# OLED_PCB_Dual_Rev1_1.net
KiCad netlist of a schematic drawn in Altium Designer
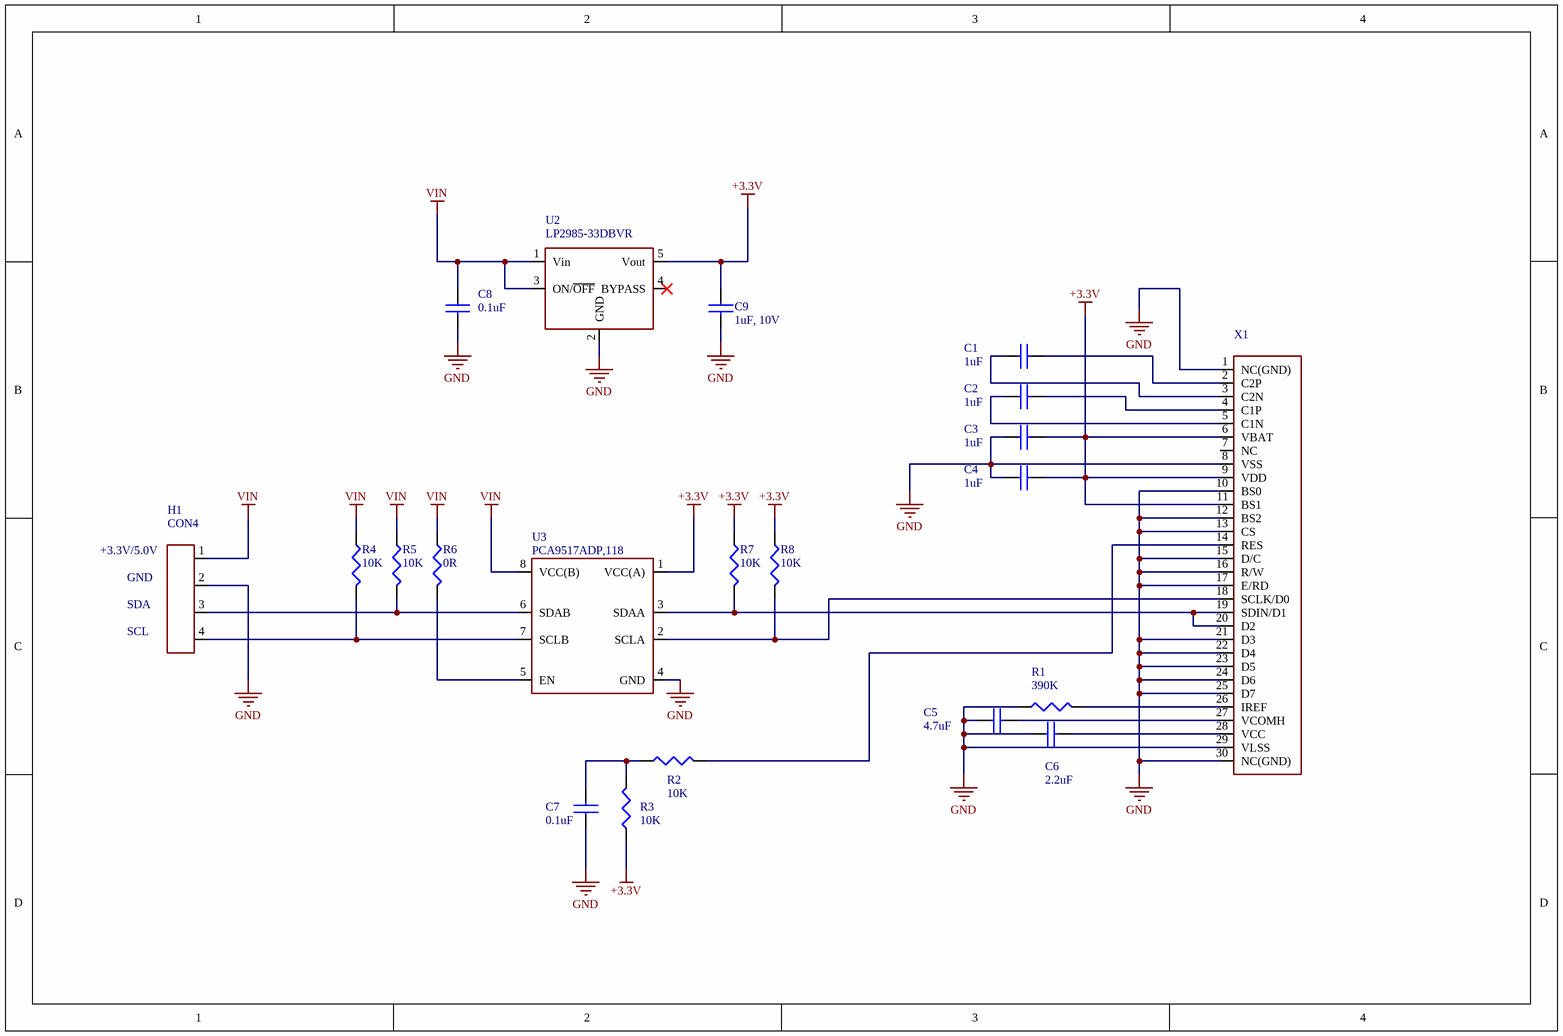
[diagram p0: OLED_PCB_Dual_Rev1_1.SchDoc]

(export (version "E")
  (design (tool "Eeschema 10.0.6"))
  (components
    (comp (ref "C1")
      (value "1uF")
      (footprint "CAPC1608X90N")
      (description "CAP 0603")
      (libsource (lib "Parts_Library") (part "CAP_0603"))
    )
    (comp (ref "C2")
      (value "1uF")
      (footprint "CAPC1608X90N")
      (description "CAP 0603")
      (libsource (lib "Parts_Library") (part "CAP_0603"))
    )
    (comp (ref "C3")
      (value "1uF")
      (footprint "CAPC1608X90N")
      (description "CAP 0603")
      (libsource (lib "Parts_Library") (part "CAP_0603"))
    )
    (comp (ref "C4")
      (value "1uF")
      (footprint "CAPC1608X90N")
      (description "CAP 0603")
      (libsource (lib "Parts_Library") (part "CAP_0603"))
    )
    (comp (ref "C5")
      (value "4.7uF")
      (footprint "CAPC1608X90N")
      (description "CAP 0603")
      (libsource (lib "Parts_Library") (part "CAP_0603"))
    )
    (comp (ref "C6")
      (value "2.2uF")
      (footprint "CAPC1608X90N")
      (description "CAP 0603")
      (libsource (lib "Parts_Library") (part "CAP_0603"))
    )
    (comp (ref "C7")
      (value "0.1uF")
      (footprint "CAPC1608X90N")
      (description "CAP 0603")
      (libsource (lib "Parts_Library") (part "CAP_0603"))
    )
    (comp (ref "C8")
      (value "0.1uF")
      (footprint "CAPC1608X90N")
      (description "CAP 0603")
      (libsource (lib "Parts_Library") (part "CAP_0603"))
    )
    (comp (ref "C9")
      (value "1uF, 10V")
      (footprint "CAPC1608X90N")
      (description "CAP CER 1UF 10V 10% X7R 0603")
      (fields (field (name "EXACT PART NUMBER") "C1608X7R1A105K") (field (name "MANUFACTURER") "TDK Corp"))
      (libsource (lib "Parts_Library") (part "C1608X7R1A105K"))
    )
    (comp (ref "H1")
      (value "CON4")
      (footprint "HDR1X4-Empty")
      (description "CONN HEADER 4POS .100\" PADS")
      (fields (field (name "PARTNUMBER") "PADS"))
      (libsource (lib "Parts_Library") (part "CON4"))
    )
    (comp (ref "R1")
      (value "390K")
      (footprint "RESC1608X55N")
      (description "RES 0603")
      (libsource (lib "Parts_Library") (part "RES_0603"))
    )
    (comp (ref "R2")
      (value "10K")
      (footprint "RESC1608X55N")
      (description "RES 0603")
      (libsource (lib "Parts_Library") (part "RES_0603"))
    )
    (comp (ref "R3")
      (value "10K")
      (footprint "RESC1608X55N")
      (description "RES 0603")
      (libsource (lib "Parts_Library") (part "RES_0603"))
    )
    (comp (ref "R4")
      (value "10K")
      (footprint "RESC1608X55N")
      (description "RES 0603")
      (libsource (lib "Parts_Library") (part "RES_0603"))
    )
    (comp (ref "R5")
      (value "10K")
      (footprint "RESC1608X55N")
      (description "RES 0603")
      (libsource (lib "Parts_Library") (part "RES_0603"))
    )
    (comp (ref "R6")
      (value "0R")
      (footprint "RESC1608X55N")
      (description "RES 0603")
      (libsource (lib "Parts_Library") (part "RES_0603"))
    )
    (comp (ref "R7")
      (value "10K")
      (footprint "RESC1608X55N")
      (description "RES 0603")
      (libsource (lib "Parts_Library") (part "RES_0603"))
    )
    (comp (ref "R8")
      (value "10K")
      (footprint "RESC1608X55N")
      (description "RES 0603")
      (libsource (lib "Parts_Library") (part "RES_0603"))
    )
    (comp (ref "U2")
      (value "LP2985-33DBVR")
      (footprint "SOT95P280X144-5N")
      (description "IC REG LDO 3.3V .15A SOT23-5")
      (fields (field (name "MANUFACTURER") "Texas Instruments"))
      (libsource (lib "Parts_Library") (part "LP2985-33DBVR"))
    )
    (comp (ref "U3")
      (value "PCA9517ADP,118")
      (footprint "TSOP65P490X110-8N")
      (description "IC I2C BUS REPEATER 8-TSSOP")
      (fields (field (name "MANUFACTURER") "Maxim"))
      (libsource (lib "Parts_Library") (part "PCA9517ADP,118"))
    )
    (comp (ref "X1")
      (value "OLED_GLASS")
      (footprint "OLED_GLASS")
      (libsource (lib "Parts_Library") (part "OLED_GLASS"))
    )
  )
  (nets
    (net (code "1") (name "+3.3V") (class "Default")
      (node (ref "C3") (pin "2") (pinfunction "2_2") (pintype "passive"))
      (node (ref "C4") (pin "2") (pinfunction "2_2") (pintype "passive"))
      (node (ref "C9") (pin "1") (pinfunction "1_1") (pintype "passive"))
      (node (ref "R3") (pin "1") (pinfunction "1_1") (pintype "passive"))
      (node (ref "R7") (pin "1") (pinfunction "1_1") (pintype "passive"))
      (node (ref "R8") (pin "1") (pinfunction "1_1") (pintype "passive"))
      (node (ref "U2") (pin "5") (pinfunction "Vout_5") (pintype "passive"))
      (node (ref "U3") (pin "1") (pinfunction "VCC(A)_1") (pintype "passive"))
      (node (ref "X1") (pin "11") (pinfunction "BS1_11") (pintype "passive"))
      (node (ref "X1") (pin "6") (pinfunction "VBAT_6") (pintype "passive"))
      (node (ref "X1") (pin "9") (pinfunction "VDD_9") (pintype "passive"))
    )
    (net (code "2") (name "GND") (class "Default")
      (node (ref "C3") (pin "1") (pinfunction "1_1") (pintype "passive"))
      (node (ref "C4") (pin "1") (pinfunction "1_1") (pintype "passive"))
      (node (ref "C5") (pin "1") (pinfunction "1_1") (pintype "passive"))
      (node (ref "C6") (pin "1") (pinfunction "1_1") (pintype "passive"))
      (node (ref "C7") (pin "1") (pinfunction "1_1") (pintype "passive"))
      (node (ref "C8") (pin "2") (pinfunction "2_2") (pintype "passive"))
      (node (ref "C9") (pin "2") (pinfunction "2_2") (pintype "passive"))
      (node (ref "H1") (pin "2") (pintype "passive"))
      (node (ref "R1") (pin "1") (pinfunction "1_1") (pintype "passive"))
      (node (ref "U2") (pin "2") (pinfunction "GND_2") (pintype "power_in"))
      (node (ref "U3") (pin "4") (pinfunction "GND_4") (pintype "passive"))
      (node (ref "X1") (pin "1") (pinfunction "NC(GND)_1") (pintype "passive"))
      (node (ref "X1") (pin "10") (pinfunction "BS0_10") (pintype "passive"))
      (node (ref "X1") (pin "12") (pinfunction "BS2_12") (pintype "passive"))
      (node (ref "X1") (pin "13") (pinfunction "CS_13") (pintype "passive"))
      (node (ref "X1") (pin "15") (pinfunction "D/C_15") (pintype "passive"))
      (node (ref "X1") (pin "16") (pinfunction "R/W_16") (pintype "passive"))
      (node (ref "X1") (pin "17") (pinfunction "E/RD_17") (pintype "passive"))
      (node (ref "X1") (pin "21") (pinfunction "D3_21") (pintype "passive"))
      (node (ref "X1") (pin "22") (pinfunction "D4_22") (pintype "passive"))
      (node (ref "X1") (pin "23") (pinfunction "D5_23") (pintype "passive"))
      (node (ref "X1") (pin "24") (pinfunction "D6_24") (pintype "passive"))
      (node (ref "X1") (pin "25") (pinfunction "D7_25") (pintype "passive"))
      (node (ref "X1") (pin "29") (pinfunction "VLSS_29") (pintype "passive"))
      (node (ref "X1") (pin "30") (pinfunction "NC(GND)_30") (pintype "passive"))
      (node (ref "X1") (pin "8") (pinfunction "VSS_8") (pintype "passive"))
    )
    (net (code "3") (name "Net-(C7-Pad2)") (class "Default")
      (node (ref "C7") (pin "2") (pinfunction "2_2") (pintype "passive"))
      (node (ref "R2") (pin "1") (pinfunction "1_1") (pintype "passive"))
      (node (ref "R3") (pin "2") (pinfunction "2_2") (pintype "passive"))
    )
    (net (code "4") (name "Net-(U3-EN)") (class "Default")
      (node (ref "R6") (pin "2") (pinfunction "2_2") (pintype "passive"))
      (node (ref "U3") (pin "5") (pinfunction "EN_5") (pintype "passive"))
    )
    (net (code "5") (name "Net-(U3-SCLA)") (class "Default")
      (node (ref "R8") (pin "2") (pinfunction "2_2") (pintype "passive"))
      (node (ref "U3") (pin "2") (pinfunction "SCLA_2") (pintype "passive"))
      (node (ref "X1") (pin "18") (pinfunction "SCLK/D0_18") (pintype "passive"))
    )
    (net (code "6") (name "Net-(U3-SCLB)") (class "Default")
      (node (ref "H1") (pin "4") (pintype "passive"))
      (node (ref "R4") (pin "2") (pinfunction "2_2") (pintype "passive"))
      (node (ref "U3") (pin "7") (pinfunction "SCLB_7") (pintype "passive"))
    )
    (net (code "7") (name "Net-(U3-SDAA)") (class "Default")
      (node (ref "R7") (pin "2") (pinfunction "2_2") (pintype "passive"))
      (node (ref "U3") (pin "3") (pinfunction "SDAA_3") (pintype "passive"))
      (node (ref "X1") (pin "19") (pinfunction "SDIN/D1_19") (pintype "passive"))
      (node (ref "X1") (pin "20") (pinfunction "D2_20") (pintype "passive"))
    )
    (net (code "8") (name "Net-(U3-SDAB)") (class "Default")
      (node (ref "H1") (pin "3") (pintype "passive"))
      (node (ref "R5") (pin "2") (pinfunction "2_2") (pintype "passive"))
      (node (ref "U3") (pin "6") (pinfunction "SDAB_6") (pintype "passive"))
    )
    (net (code "9") (name "Net-(X1-C1N)") (class "Default")
      (node (ref "C2") (pin "1") (pinfunction "1_1") (pintype "passive"))
      (node (ref "X1") (pin "5") (pinfunction "C1N_5") (pintype "passive"))
    )
    (net (code "10") (name "Net-(X1-C1P)") (class "Default")
      (node (ref "C2") (pin "2") (pinfunction "2_2") (pintype "passive"))
      (node (ref "X1") (pin "4") (pinfunction "C1P_4") (pintype "passive"))
    )
    (net (code "11") (name "Net-(X1-C2N)") (class "Default")
      (node (ref "C1") (pin "1") (pinfunction "1_1") (pintype "passive"))
      (node (ref "X1") (pin "3") (pinfunction "C2N_3") (pintype "passive"))
    )
    (net (code "12") (name "Net-(X1-C2P)") (class "Default")
      (node (ref "C1") (pin "2") (pinfunction "2_2") (pintype "passive"))
      (node (ref "X1") (pin "2") (pinfunction "C2P_2") (pintype "passive"))
    )
    (net (code "13") (name "Net-(X1-IREF)") (class "Default")
      (node (ref "R1") (pin "2") (pinfunction "2_2") (pintype "passive"))
      (node (ref "X1") (pin "26") (pinfunction "IREF_26") (pintype "passive"))
    )
    (net (code "14") (name "Net-(X1-RES)") (class "Default")
      (node (ref "R2") (pin "2") (pinfunction "2_2") (pintype "passive"))
      (node (ref "X1") (pin "14") (pinfunction "RES_14") (pintype "passive"))
    )
    (net (code "15") (name "Net-(X1-VCC)") (class "Default")
      (node (ref "C6") (pin "2") (pinfunction "2_2") (pintype "passive"))
      (node (ref "X1") (pin "28") (pinfunction "VCC_28") (pintype "passive"))
    )
    (net (code "16") (name "Net-(X1-VCOMH)") (class "Default")
      (node (ref "C5") (pin "2") (pinfunction "2_2") (pintype "passive"))
      (node (ref "X1") (pin "27") (pinfunction "VCOMH_27") (pintype "passive"))
    )
    (net (code "17") (name "VIN") (class "Default")
      (node (ref "C8") (pin "1") (pinfunction "1_1") (pintype "passive"))
      (node (ref "H1") (pin "1") (pintype "passive"))
      (node (ref "R4") (pin "1") (pinfunction "1_1") (pintype "passive"))
      (node (ref "R5") (pin "1") (pinfunction "1_1") (pintype "passive"))
      (node (ref "R6") (pin "1") (pinfunction "1_1") (pintype "passive"))
      (node (ref "U2") (pin "1") (pinfunction "Vin_1") (pintype "passive"))
      (node (ref "U2") (pin "3") (pinfunction "ON/~{OFF}_3") (pintype "passive"))
      (node (ref "U3") (pin "8") (pinfunction "VCC(B)_8") (pintype "power_in"))
    )
    (net (code "18") (name "unconnected-(U2-BYPASS-Pad4)") (class "Default")
      (node (ref "U2") (pin "4") (pinfunction "BYPASS_4") (pintype "passive+no_connect"))
    )
    (net (code "19") (name "unconnected-(X1-NC-Pad7)") (class "Default")
      (node (ref "X1") (pin "7") (pinfunction "NC_7") (pintype "passive"))
    )
  )
)
